# ESP32_fire.net
KiCad netlist of a schematic drawn in EasyEDA
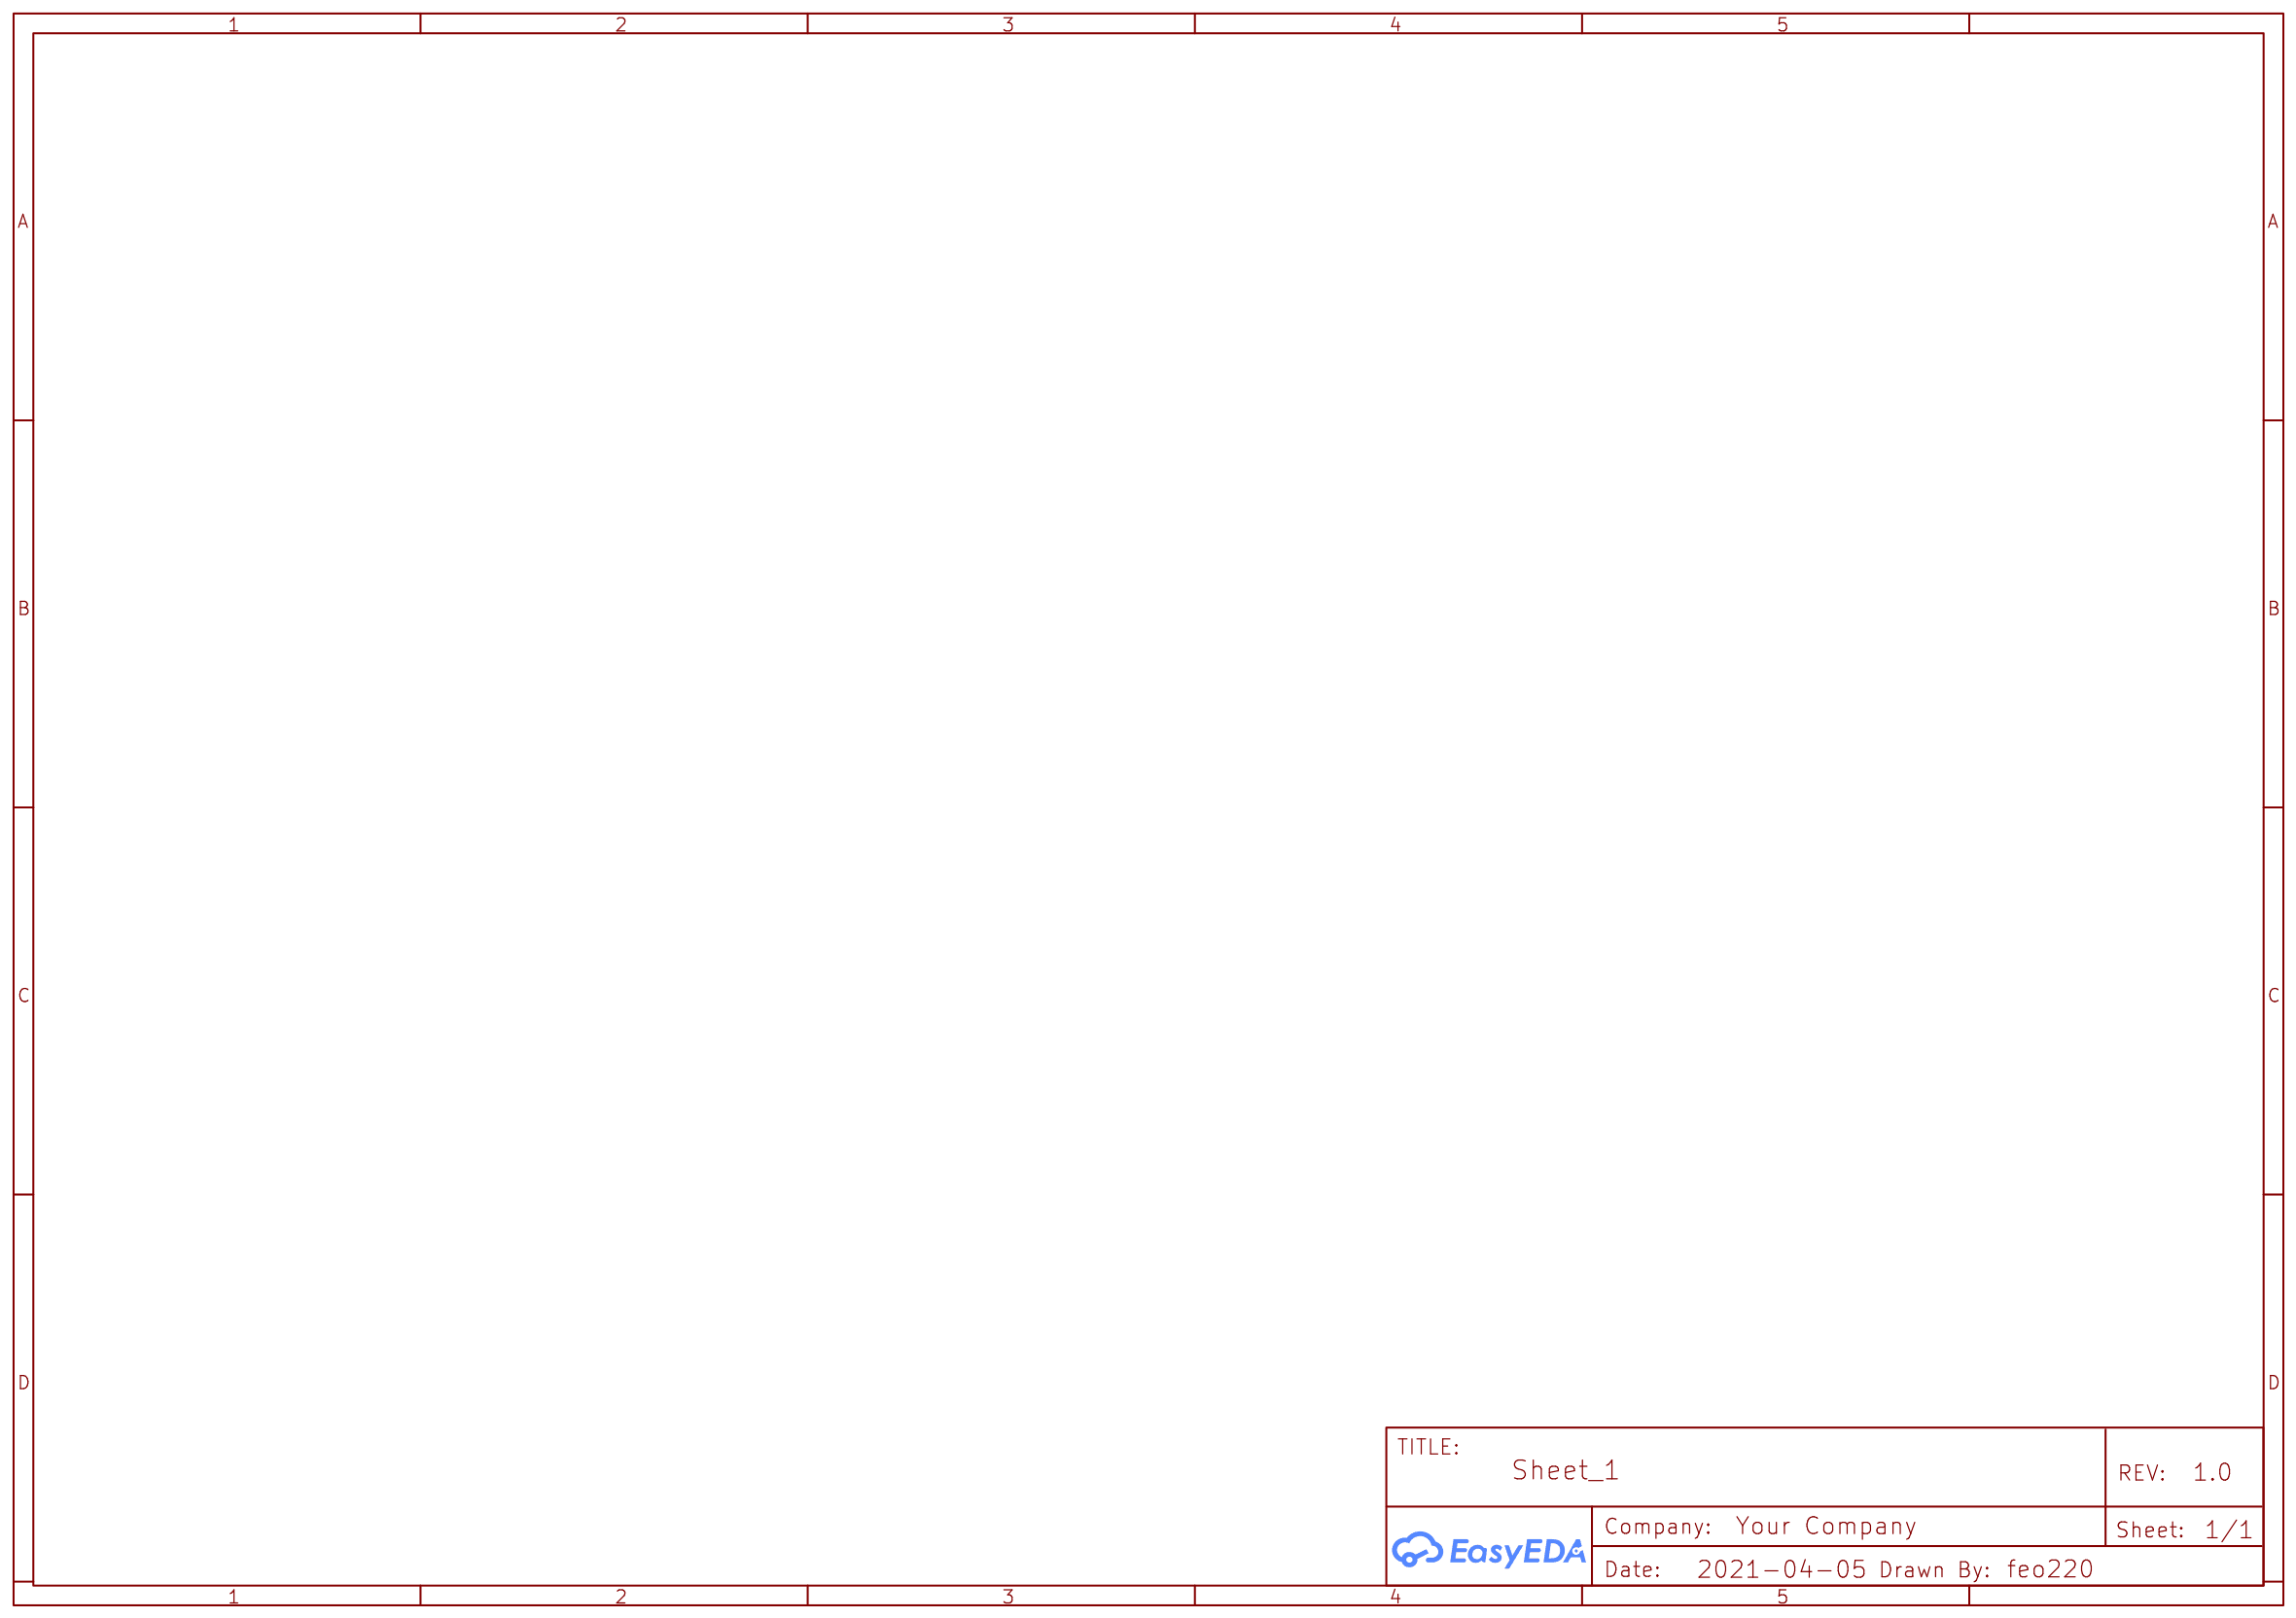
[diagram p0: Sheet_1]
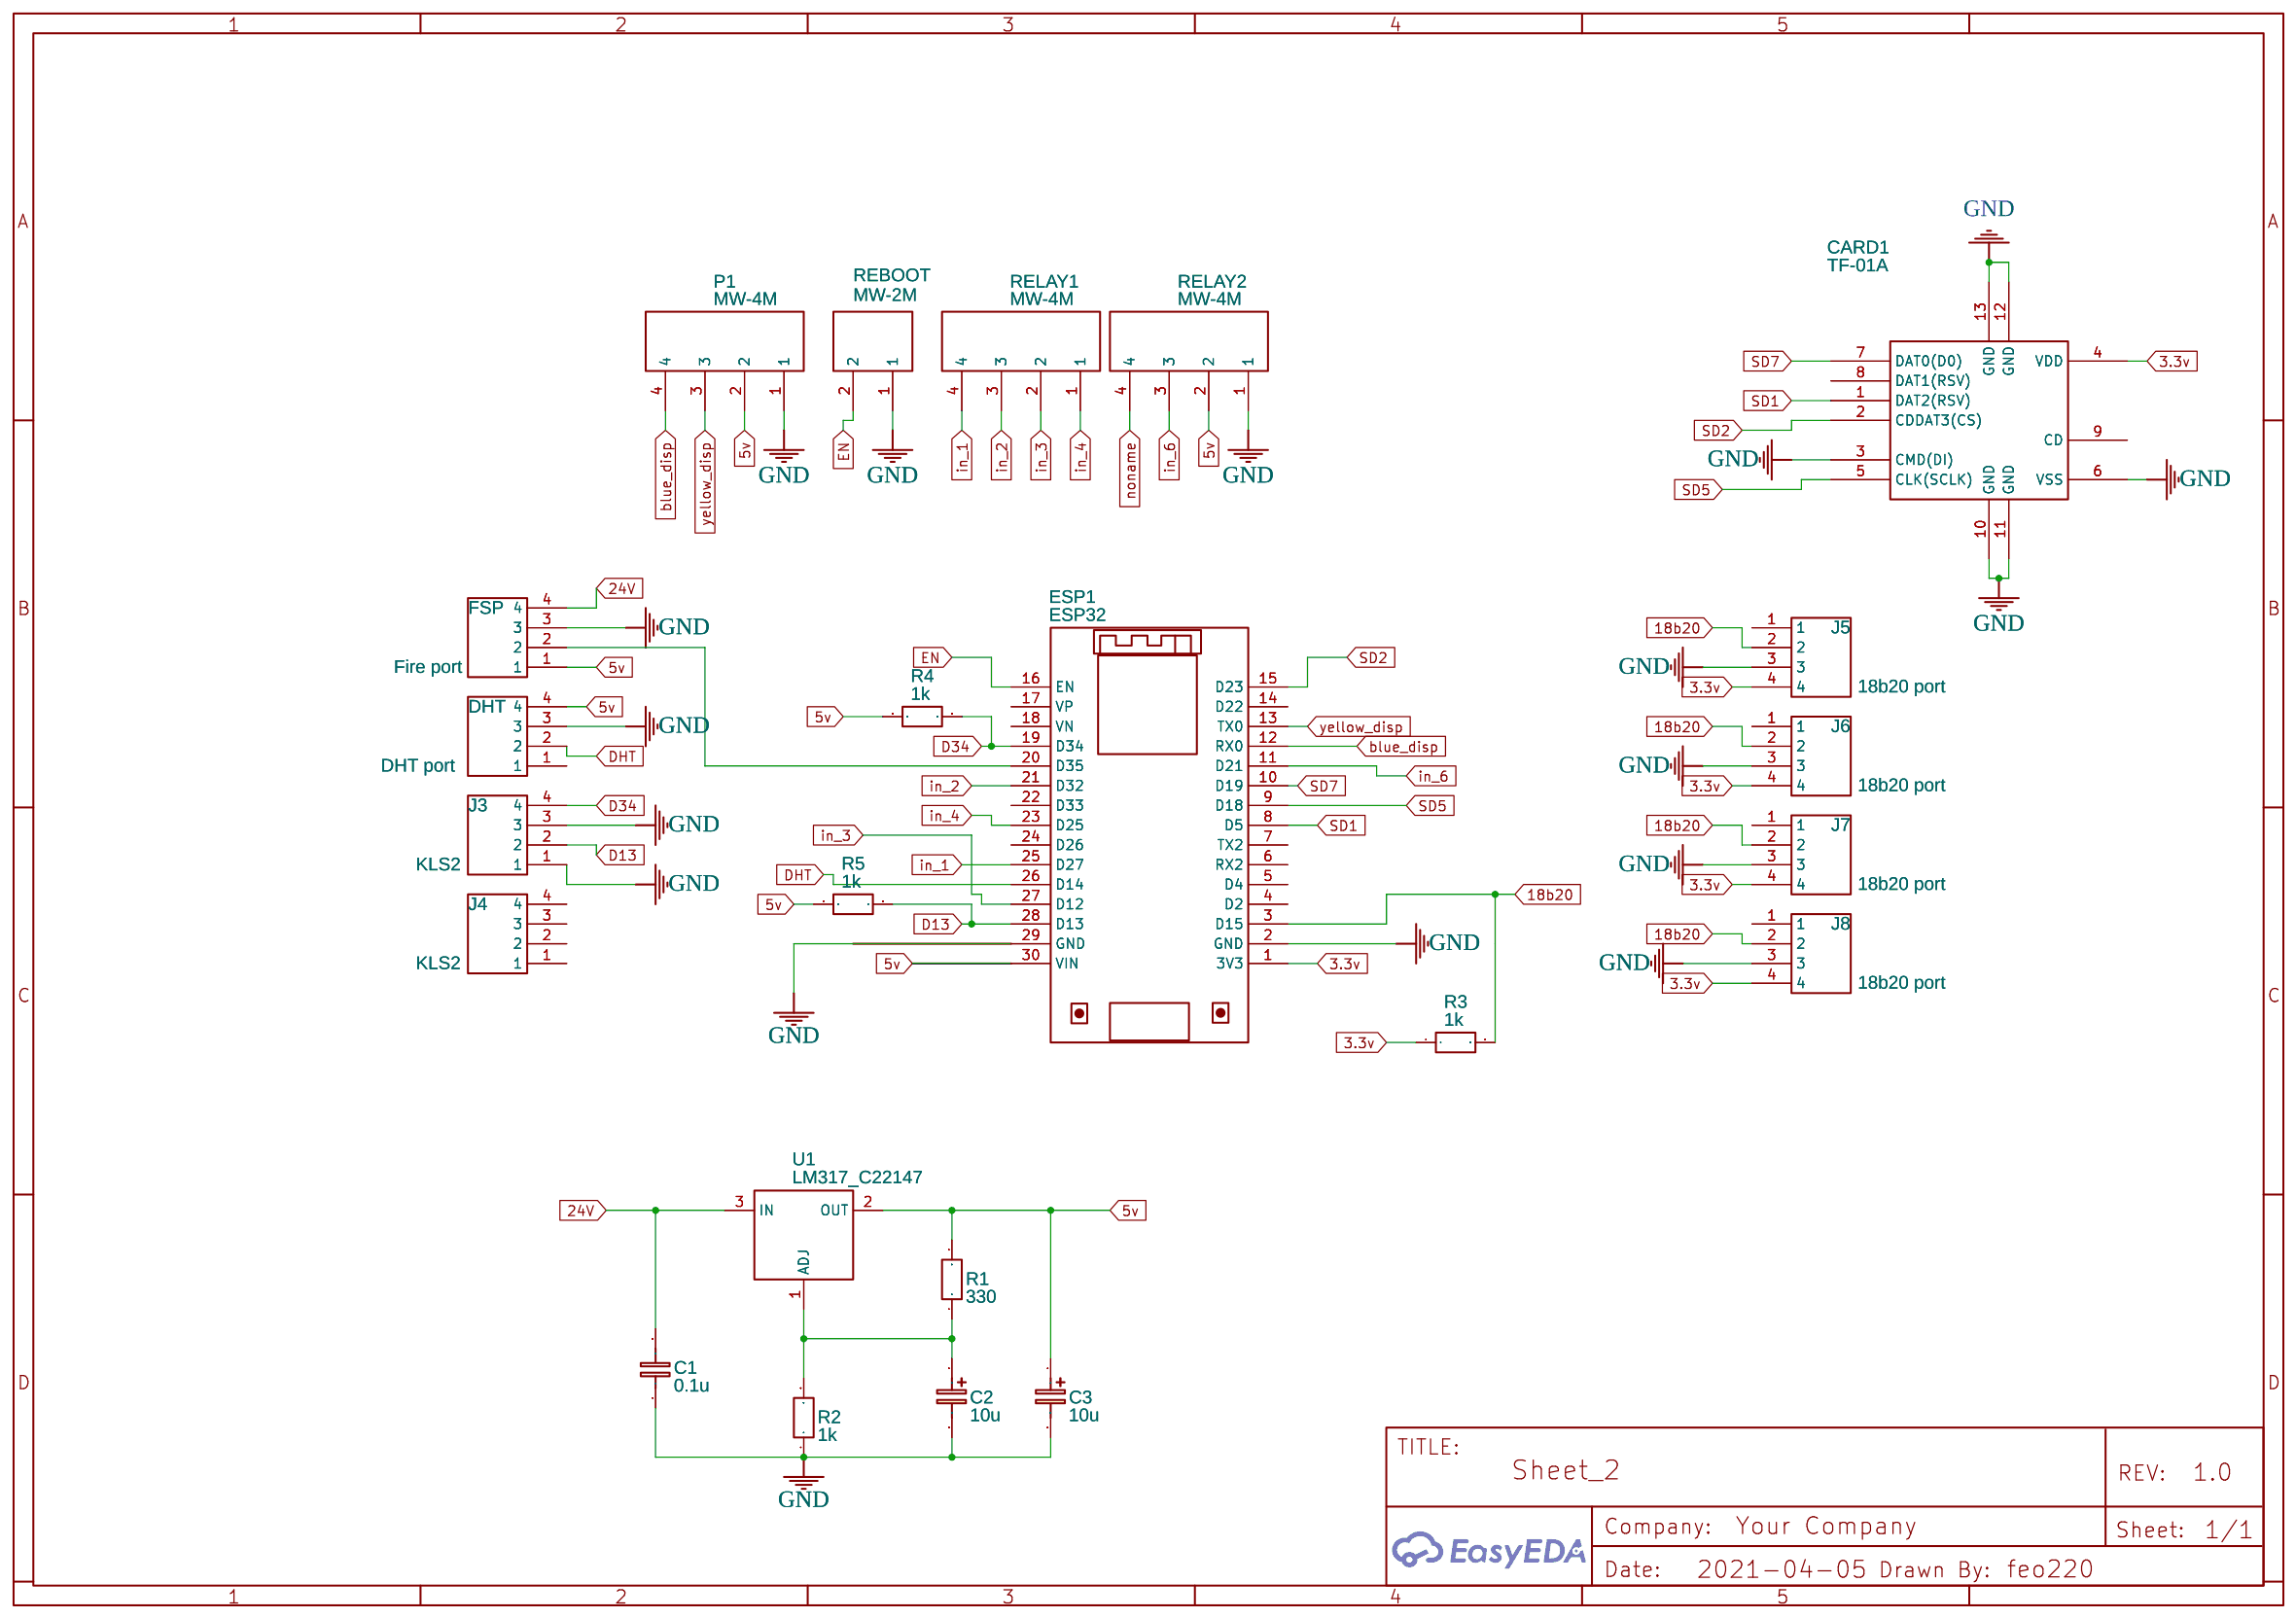
[diagram p1: Sheet_2]

(export (version "E")
  (design (tool "Eeschema 10.0.6"))
  (components
    (comp (ref "C1") (value "0.1u") (libsource (lib "") (part "C_0603_EU")))
    (comp (ref "C2") (value "10u") (libsource (lib "") (part "C_Tan_SMD_A_EU_1")))
    (comp (ref "C3") (value "10u") (libsource (lib "") (part "C_Tan_SMD_A_EU")))
    (comp (ref "CARD1")
      (value "TF-01A")
      (fields (field (name "BOM_Supplier Part") "C91145"))
      (libsource (lib "") (part "TF-01A"))
    )
    (comp (ref "DHT")
      (value "DHT port")
      (fields (field (name "BOM_Manufacturer Part") "KLS2-103-5.00-04P-4S"))
      (libsource (lib "") (part "KLS2-103-5.00-04P-4S_3"))
    )
    (comp (ref "ESP1")
      (value "ESP32")
      (fields (field (name "BOM_Manufacturer Part") "ESP32-DEVKIT-C"))
      (libsource (lib "") (part "ESP32"))
    )
    (comp (ref "FSP")
      (value "Fire port")
      (fields (field (name "BOM_Manufacturer Part") "KLS2-103-5.00-04P-4S"))
      (libsource (lib "") (part "KLS2-103-5.00-04P-4S_2"))
    )
    (comp (ref "J3")
      (value "KLS2")
      (fields (field (name "BOM_Manufacturer Part") "KLS2-103-5.00-04P-4S"))
      (libsource (lib "") (part "KLS2-103-5.00-04P-4S_1"))
    )
    (comp (ref "J4")
      (value "KLS2")
      (fields (field (name "BOM_Manufacturer Part") "KLS2-103-5.00-04P-4S"))
      (libsource (lib "") (part "KLS2-103-5.00-04P-4S_1"))
    )
    (comp (ref "J5")
      (value "18b20 port")
      (fields (field (name "BOM_Manufacturer Part") "KLS2-103-5.00-04P-4S"))
      (libsource (lib "") (part "KLS2-103-5.00-04P-4S"))
    )
    (comp (ref "J6")
      (value "18b20 port")
      (fields (field (name "BOM_Manufacturer Part") "KLS2-103-5.00-04P-4S"))
      (libsource (lib "") (part "KLS2-103-5.00-04P-4S"))
    )
    (comp (ref "J7")
      (value "18b20 port")
      (fields (field (name "BOM_Manufacturer Part") "KLS2-103-5.00-04P-4S"))
      (libsource (lib "") (part "KLS2-103-5.00-04P-4S"))
    )
    (comp (ref "J8")
      (value "18b20 port")
      (fields (field (name "BOM_Manufacturer Part") "KLS2-103-5.00-04P-4S"))
      (libsource (lib "") (part "KLS2-103-5.00-04P-4S"))
    )
    (comp (ref "P1")
      (value "MW-4M")
      (fields (field (name "BOM_Manufacturer Part") "DG306-5.0-02P-12-00A(H)"))
      (libsource (lib "") (part "MW-4M_1"))
    )
    (comp (ref "R1") (value "330") (libsource (lib "") (part "R_0603_EU_1")))
    (comp (ref "R2") (value "1k") (libsource (lib "") (part "R_0603_EU_1")))
    (comp (ref "R3") (value "1k") (libsource (lib "") (part "R_0603_EU")))
    (comp (ref "R4") (value "1k") (libsource (lib "") (part "R_0603_EU")))
    (comp (ref "R5") (value "1k") (libsource (lib "") (part "R_0603_EU")))
    (comp (ref "REBOOT")
      (value "MW-2M")
      (fields (field (name "BOM_Manufacturer Part") "DG306-5.0-02P-12-00A(H)"))
      (libsource (lib "") (part "MW-2M"))
    )
    (comp (ref "RELAY1")
      (value "MW-4M")
      (fields (field (name "BOM_Manufacturer Part") "DG306-5.0-02P-12-00A(H)"))
      (libsource (lib "") (part "MW-4M"))
    )
    (comp (ref "RELAY2")
      (value "MW-4M")
      (fields (field (name "BOM_Manufacturer Part") "DG306-5.0-02P-12-00A(H)"))
      (libsource (lib "") (part "MW-4M"))
    )
    (comp (ref "U1")
      (value "LM317_C22147")
      (fields (field (name "BOM_Manufacturer Part") "LM317") (field (name "BOM_Supplier Part") "C22147"))
      (libsource (lib "") (part "LM317_C22147"))
    )
  )
  (nets
    (net (code "1") (name "3.3v") (class "Default")
      (node (ref "CARD1") (pin "4") (pinfunction "VDD_4") (pintype "input"))
      (node (ref "ESP1") (pin "1") (pinfunction "3V3_1") (pintype "unspecified"))
      (node (ref "J5") (pin "4") (pinfunction "4_4") (pintype "unspecified"))
      (node (ref "J6") (pin "4") (pinfunction "4_4") (pintype "unspecified"))
      (node (ref "J7") (pin "4") (pinfunction "4_4") (pintype "unspecified"))
      (node (ref "J8") (pin "4") (pinfunction "4_4") (pintype "unspecified"))
      (node (ref "R3") (pin "1") (pinfunction "1_1") (pintype "unspecified"))
    )
    (net (code "2") (name "5v") (class "Default")
      (node (ref "C3") (pin "1") (pinfunction "1_1") (pintype "unspecified"))
      (node (ref "DHT") (pin "4") (pinfunction "4_4") (pintype "unspecified"))
      (node (ref "ESP1") (pin "30") (pinfunction "VIN_30") (pintype "unspecified"))
      (node (ref "FSP") (pin "1") (pinfunction "1_1") (pintype "unspecified"))
      (node (ref "P1") (pin "2") (pinfunction "2_2") (pintype "unspecified"))
      (node (ref "R1") (pin "2") (pinfunction "2_2") (pintype "unspecified"))
      (node (ref "R4") (pin "1") (pinfunction "1_1") (pintype "unspecified"))
      (node (ref "R5") (pin "1") (pinfunction "1_1") (pintype "unspecified"))
      (node (ref "RELAY2") (pin "2") (pinfunction "2_2") (pintype "unspecified"))
      (node (ref "U1") (pin "2") (pinfunction "OUT_2") (pintype "unspecified"))
    )
    (net (code "3") (name "18b20") (class "Default")
      (node (ref "ESP1") (pin "3") (pinfunction "D15_3") (pintype "unspecified"))
      (node (ref "J5") (pin "2") (pinfunction "2_2") (pintype "unspecified"))
      (node (ref "J6") (pin "2") (pinfunction "2_2") (pintype "unspecified"))
      (node (ref "J7") (pin "2") (pinfunction "2_2") (pintype "unspecified"))
      (node (ref "J8") (pin "2") (pinfunction "2_2") (pintype "unspecified"))
      (node (ref "R3") (pin "2") (pinfunction "2_2") (pintype "unspecified"))
    )
    (net (code "4") (name "24V") (class "Default")
      (node (ref "C1") (pin "2") (pinfunction "2_2") (pintype "unspecified"))
      (node (ref "FSP") (pin "4") (pinfunction "4_4") (pintype "unspecified"))
      (node (ref "U1") (pin "3") (pinfunction "IN_3") (pintype "input"))
    )
    (net (code "5") (name "D13") (class "Default")
      (node (ref "ESP1") (pin "28") (pinfunction "D13_28") (pintype "unspecified"))
      (node (ref "J3") (pin "2") (pinfunction "2_2") (pintype "unspecified"))
      (node (ref "R5") (pin "2") (pinfunction "2_2") (pintype "unspecified"))
    )
    (net (code "6") (name "D34") (class "Default")
      (node (ref "ESP1") (pin "19") (pinfunction "D34_19") (pintype "unspecified"))
      (node (ref "J3") (pin "4") (pinfunction "4_4") (pintype "unspecified"))
      (node (ref "R4") (pin "2") (pinfunction "2_2") (pintype "unspecified"))
    )
    (net (code "7") (name "DHT") (class "Default")
      (node (ref "DHT") (pin "2") (pinfunction "2_2") (pintype "unspecified"))
      (node (ref "ESP1") (pin "26") (pinfunction "D14_26") (pintype "unspecified"))
    )
    (net (code "8") (name "EN") (class "Default")
      (node (ref "ESP1") (pin "16") (pinfunction "EN_16") (pintype "unspecified"))
      (node (ref "REBOOT") (pin "2") (pinfunction "2_2") (pintype "unspecified"))
    )
    (net (code "9") (name "GND") (class "Default")
      (node (ref "C1") (pin "1") (pinfunction "1_1") (pintype "unspecified"))
      (node (ref "C2") (pin "2") (pinfunction "2_2") (pintype "unspecified"))
      (node (ref "C3") (pin "2") (pinfunction "2_2") (pintype "unspecified"))
      (node (ref "CARD1") (pin "10") (pinfunction "GND_10") (pintype "input"))
      (node (ref "CARD1") (pin "11") (pinfunction "GND_11") (pintype "input"))
      (node (ref "CARD1") (pin "12") (pinfunction "GND_12") (pintype "input"))
      (node (ref "CARD1") (pin "13") (pinfunction "GND_13") (pintype "input"))
      (node (ref "CARD1") (pin "3") (pinfunction "CMD(DI)_3") (pintype "input"))
      (node (ref "CARD1") (pin "6") (pinfunction "VSS_6") (pintype "input"))
      (node (ref "DHT") (pin "3") (pinfunction "3_3") (pintype "unspecified"))
      (node (ref "ESP1") (pin "2") (pinfunction "GND_2") (pintype "unspecified"))
      (node (ref "ESP1") (pin "29") (pinfunction "GND_29") (pintype "unspecified"))
      (node (ref "FSP") (pin "3") (pinfunction "3_3") (pintype "unspecified"))
      (node (ref "J3") (pin "1") (pinfunction "1_1") (pintype "unspecified"))
      (node (ref "J3") (pin "3") (pinfunction "3_3") (pintype "unspecified"))
      (node (ref "J5") (pin "3") (pinfunction "3_3") (pintype "unspecified"))
      (node (ref "J6") (pin "3") (pinfunction "3_3") (pintype "unspecified"))
      (node (ref "J7") (pin "3") (pinfunction "3_3") (pintype "unspecified"))
      (node (ref "J8") (pin "3") (pinfunction "3_3") (pintype "unspecified"))
      (node (ref "P1") (pin "1") (pinfunction "1_1") (pintype "unspecified"))
      (node (ref "R2") (pin "1") (pinfunction "1_1") (pintype "unspecified"))
      (node (ref "REBOOT") (pin "1") (pinfunction "1_1") (pintype "unspecified"))
      (node (ref "RELAY2") (pin "1") (pinfunction "1_1") (pintype "unspecified"))
    )
    (net (code "10") (name "Net-(ESP1-D35)") (class "Default")
      (node (ref "ESP1") (pin "20") (pinfunction "D35_20") (pintype "unspecified"))
      (node (ref "FSP") (pin "2") (pinfunction "2_2") (pintype "unspecified"))
    )
    (net (code "11") (name "Net-(U1-ADJ)") (class "Default")
      (node (ref "C2") (pin "1") (pinfunction "1_1") (pintype "unspecified"))
      (node (ref "R1") (pin "1") (pinfunction "1_1") (pintype "unspecified"))
      (node (ref "R2") (pin "2") (pinfunction "2_2") (pintype "unspecified"))
      (node (ref "U1") (pin "1") (pinfunction "ADJ_1") (pintype "input"))
    )
    (net (code "12") (name "SD1") (class "Default")
      (node (ref "CARD1") (pin "1") (pinfunction "DAT2(RSV)_1") (pintype "bidirectional"))
      (node (ref "ESP1") (pin "8") (pinfunction "D5_8") (pintype "unspecified"))
    )
    (net (code "13") (name "SD2") (class "Default")
      (node (ref "CARD1") (pin "2") (pinfunction "CDDAT3(CS)_2") (pintype "bidirectional"))
      (node (ref "ESP1") (pin "15") (pinfunction "D23_15") (pintype "unspecified"))
    )
    (net (code "14") (name "SD5") (class "Default")
      (node (ref "CARD1") (pin "5") (pinfunction "CLK(SCLK)_5") (pintype "input"))
      (node (ref "ESP1") (pin "9") (pinfunction "D18_9") (pintype "unspecified"))
    )
    (net (code "15") (name "SD7") (class "Default")
      (node (ref "CARD1") (pin "7") (pinfunction "DAT0(D0)_7") (pintype "bidirectional"))
      (node (ref "ESP1") (pin "10") (pinfunction "D19_10") (pintype "unspecified"))
    )
    (net (code "16") (name "blue_disp") (class "Default")
      (node (ref "ESP1") (pin "12") (pinfunction "RX0_12") (pintype "unspecified"))
      (node (ref "P1") (pin "4") (pinfunction "4_4") (pintype "unspecified"))
    )
    (net (code "17") (name "in_1") (class "Default")
      (node (ref "ESP1") (pin "25") (pinfunction "D27_25") (pintype "unspecified"))
      (node (ref "RELAY1") (pin "4") (pinfunction "4_4") (pintype "unspecified"))
    )
    (net (code "18") (name "in_2") (class "Default")
      (node (ref "ESP1") (pin "21") (pinfunction "D32_21") (pintype "unspecified"))
      (node (ref "RELAY1") (pin "3") (pinfunction "3_3") (pintype "unspecified"))
    )
    (net (code "19") (name "in_3") (class "Default")
      (node (ref "ESP1") (pin "27") (pinfunction "D12_27") (pintype "unspecified"))
      (node (ref "RELAY1") (pin "2") (pinfunction "2_2") (pintype "unspecified"))
    )
    (net (code "20") (name "in_4") (class "Default")
      (node (ref "ESP1") (pin "23") (pinfunction "D25_23") (pintype "unspecified"))
      (node (ref "RELAY1") (pin "1") (pinfunction "1_1") (pintype "unspecified"))
    )
    (net (code "21") (name "in_6") (class "Default")
      (node (ref "ESP1") (pin "11") (pinfunction "D21_11") (pintype "unspecified"))
      (node (ref "RELAY2") (pin "3") (pinfunction "3_3") (pintype "unspecified"))
    )
    (net (code "22") (name "noname") (class "Default")
      (node (ref "RELAY2") (pin "4") (pinfunction "4_4") (pintype "unspecified"))
    )
    (net (code "23") (name "unconnected-(CARD1-CD-Pad9)") (class "Default")
      (node (ref "CARD1") (pin "9") (pinfunction "CD_9") (pintype "input"))
    )
    (net (code "24") (name "unconnected-(CARD1-DAT1(RSV)-Pad8)") (class "Default")
      (node (ref "CARD1") (pin "8") (pinfunction "DAT1(RSV)_8") (pintype "bidirectional"))
    )
    (net (code "25") (name "unconnected-(DHT-Pad1)") (class "Default")
      (node (ref "DHT") (pin "1") (pinfunction "1_1") (pintype "unspecified"))
    )
    (net (code "26") (name "unconnected-(ESP1-D2-Pad4)") (class "Default")
      (node (ref "ESP1") (pin "4") (pinfunction "D2_4") (pintype "unspecified"))
    )
    (net (code "27") (name "unconnected-(ESP1-D4-Pad5)") (class "Default")
      (node (ref "ESP1") (pin "5") (pinfunction "D4_5") (pintype "unspecified"))
    )
    (net (code "28") (name "unconnected-(ESP1-D22-Pad14)") (class "Default")
      (node (ref "ESP1") (pin "14") (pinfunction "D22_14") (pintype "unspecified"))
    )
    (net (code "29") (name "unconnected-(ESP1-D26-Pad24)") (class "Default")
      (node (ref "ESP1") (pin "24") (pinfunction "D26_24") (pintype "unspecified"))
    )
    (net (code "30") (name "unconnected-(ESP1-D33-Pad22)") (class "Default")
      (node (ref "ESP1") (pin "22") (pinfunction "D33_22") (pintype "unspecified"))
    )
    (net (code "31") (name "unconnected-(ESP1-RX2-Pad6)") (class "Default")
      (node (ref "ESP1") (pin "6") (pinfunction "RX2_6") (pintype "unspecified"))
    )
    (net (code "32") (name "unconnected-(ESP1-TX2-Pad7)") (class "Default")
      (node (ref "ESP1") (pin "7") (pinfunction "TX2_7") (pintype "unspecified"))
    )
    (net (code "33") (name "unconnected-(ESP1-VN-Pad18)") (class "Default")
      (node (ref "ESP1") (pin "18") (pinfunction "VN_18") (pintype "unspecified"))
    )
    (net (code "34") (name "unconnected-(ESP1-VP-Pad17)") (class "Default")
      (node (ref "ESP1") (pin "17") (pinfunction "VP_17") (pintype "unspecified"))
    )
    (net (code "35") (name "unconnected-(J4-Pad1)") (class "Default")
      (node (ref "J4") (pin "1") (pinfunction "1_1") (pintype "unspecified"))
    )
    (net (code "36") (name "unconnected-(J4-Pad2)") (class "Default")
      (node (ref "J4") (pin "2") (pinfunction "2_2") (pintype "unspecified"))
    )
    (net (code "37") (name "unconnected-(J4-Pad3)") (class "Default")
      (node (ref "J4") (pin "3") (pinfunction "3_3") (pintype "unspecified"))
    )
    (net (code "38") (name "unconnected-(J4-Pad4)") (class "Default")
      (node (ref "J4") (pin "4") (pinfunction "4_4") (pintype "unspecified"))
    )
    (net (code "39") (name "unconnected-(J5-Pad1)") (class "Default")
      (node (ref "J5") (pin "1") (pinfunction "1_1") (pintype "unspecified"))
    )
    (net (code "40") (name "unconnected-(J6-Pad1)") (class "Default")
      (node (ref "J6") (pin "1") (pinfunction "1_1") (pintype "unspecified"))
    )
    (net (code "41") (name "unconnected-(J7-Pad1)") (class "Default")
      (node (ref "J7") (pin "1") (pinfunction "1_1") (pintype "unspecified"))
    )
    (net (code "42") (name "unconnected-(J8-Pad1)") (class "Default")
      (node (ref "J8") (pin "1") (pinfunction "1_1") (pintype "unspecified"))
    )
    (net (code "43") (name "yellow_disp") (class "Default")
      (node (ref "ESP1") (pin "13") (pinfunction "TX0_13") (pintype "unspecified"))
      (node (ref "P1") (pin "3") (pinfunction "3_3") (pintype "unspecified"))
    )
  )
)
